# 12v6abuckconverter.net
KiCad netlist of a schematic drawn in EAGLE
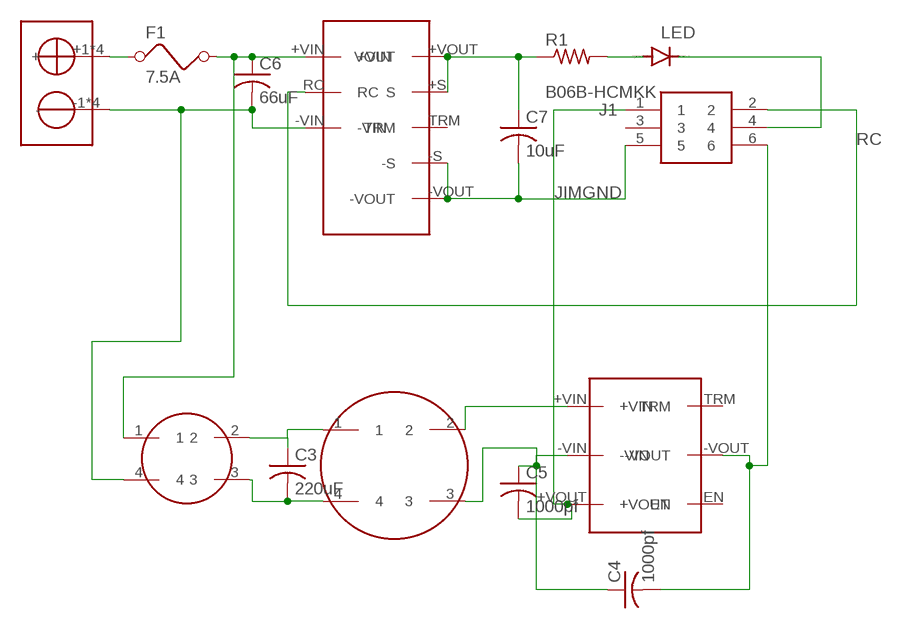
[diagram p0: schematic, sheet 1]

(export (version "E")
  (design (tool "Eeschema 10.0.6"))
  (components
    (comp (ref "BUCK150UH")
      (value "CMNMODECHOKE150UH")
      (footprint "eagle-import:CMNMODECHOKE150UH")
      (libsource (lib "eagle-import") (part "CMNMODECHOKE150UH"))
    )
    (comp (ref "C3")
      (value "220uF")
      (footprint "eagle-import:C0805")
      (libsource (lib "eagle-import") (part "C-USC0805"))
    )
    (comp (ref "C4")
      (value "1000pf")
      (footprint "eagle-import:C0805")
      (libsource (lib "eagle-import") (part "C-USC0805"))
    )
    (comp (ref "C5")
      (value "1000pf")
      (footprint "eagle-import:C0805")
      (libsource (lib "eagle-import") (part "C-USC0805"))
    )
    (comp (ref "C6")
      (value "66uF")
      (footprint "eagle-import:C0805")
      (libsource (lib "eagle-import") (part "C-USC0805"))
    )
    (comp (ref "C7")
      (value "10uF")
      (footprint "eagle-import:C0805")
      (libsource (lib "eagle-import") (part "C-USC0805"))
    )
    (comp (ref "D1")
      (value "BYV95")
      (footprint "eagle-import:SOD57-10")
      (libsource (lib "eagle-import") (part "BYV95"))
    )
    (comp (ref "F1")
      (value "7.5A")
      (footprint "eagle-import:FUSE")
      (libsource (lib "eagle-import") (part "FUSE"))
    )
    (comp (ref "J1")
      (value "B06B-HCMKK")
      (footprint "eagle-import:B06BHCMKK")
      (fields (field (name "MOUSER_PART_NUMBER") "306-B06B-HCMKK"))
      (libsource (lib "eagle-import") (part "B06B-HCMKK"))
    )
    (comp (ref "R1")
      (value "R-US_R0805")
      (footprint "eagle-import:R0805")
      (libsource (lib "eagle-import") (part "R-US_R0805"))
    )
    (comp (ref "U$1")
      (value "12V6ABUCKCONVERTER")
      (footprint "eagle-import:12V6ABUCKCONVERTER")
      (libsource (lib "eagle-import") (part "12V6ABUCKCONVERTER"))
    )
    (comp (ref "U$2")
      (value "SB50")
      (footprint "eagle-import:MINI-SB-50")
      (libsource (lib "eagle-import") (part "SB50"))
    )
    (comp (ref "U$3")
      (value "BUCK1.6A")
      (footprint "eagle-import:BUCK1.6A")
      (libsource (lib "eagle-import") (part "BUCK1.6A"))
    )
    (comp (ref "U$4")
      (value "CMNMODECHOKE1.2MH")
      (footprint "eagle-import:CMNMODECHOKE1.2MH")
      (libsource (lib "eagle-import") (part "CMNMODECHOKE1.2MH"))
    )
  )
  (nets
    (net (code "1") (name "/JIMGND") (class "Default")
      (node (ref "C7") (pin "2") (pinfunction "2_2") (pintype "passive"))
      (node (ref "J1") (pin "5") (pinfunction "5_5") (pintype "bidirectional"))
      (node (ref "U$1") (pin "-S") (pinfunction "-S_-S") (pintype "bidirectional"))
      (node (ref "U$1") (pin "-VOUT") (pinfunction "-VOUT_-VOUT") (pintype "bidirectional"))
    )
    (net (code "2") (name "/LED") (class "Default")
      (node (ref "D1") (pin "C") (pinfunction "C_C") (pintype "passive"))
      (node (ref "J1") (pin "4") (pinfunction "4_4") (pintype "bidirectional"))
    )
    (net (code "3") (name "/RC") (class "Default")
      (node (ref "J1") (pin "2") (pinfunction "2_2") (pintype "bidirectional"))
      (node (ref "U$1") (pin "RC") (pinfunction "RC_RC") (pintype "bidirectional"))
    )
    (net (code "4") (name "Net-(BUCK150UH-Pad1)") (class "Default")
      (node (ref "BUCK150UH") (pin "1") (pinfunction "1_1") (pintype "bidirectional"))
      (node (ref "C6") (pin "1") (pinfunction "1_1") (pintype "passive"))
      (node (ref "F1") (pin "2") (pinfunction "2_2") (pintype "passive"))
      (node (ref "U$1") (pin "+VIN") (pinfunction "+VIN_+VIN") (pintype "bidirectional"))
    )
    (net (code "5") (name "Net-(BUCK150UH-Pad2)") (class "Default")
      (node (ref "BUCK150UH") (pin "2") (pinfunction "2_2") (pintype "bidirectional"))
      (node (ref "C3") (pin "1") (pinfunction "1_1") (pintype "passive"))
      (node (ref "U$4") (pin "1") (pinfunction "1_1") (pintype "bidirectional"))
    )
    (net (code "6") (name "Net-(BUCK150UH-Pad3)") (class "Default")
      (node (ref "BUCK150UH") (pin "3") (pinfunction "3_3") (pintype "bidirectional"))
      (node (ref "C3") (pin "2") (pinfunction "2_2") (pintype "passive"))
      (node (ref "U$4") (pin "4") (pinfunction "4_4") (pintype "bidirectional"))
    )
    (net (code "7") (name "Net-(BUCK150UH-Pad4)") (class "Default")
      (node (ref "BUCK150UH") (pin "4") (pinfunction "4_4") (pintype "bidirectional"))
      (node (ref "C6") (pin "2") (pinfunction "2_2") (pintype "passive"))
      (node (ref "U$1") (pin "-VIN") (pinfunction "-VIN_-VIN") (pintype "bidirectional"))
      (node (ref "U$2") (pin "-1") (pinfunction "-_-1") (pintype "bidirectional"))
      (node (ref "U$2") (pin "-2") (pinfunction "-_-2") (pintype "bidirectional"))
      (node (ref "U$2") (pin "-3") (pinfunction "-_-3") (pintype "bidirectional"))
      (node (ref "U$2") (pin "-4") (pinfunction "-_-4") (pintype "bidirectional"))
    )
    (net (code "8") (name "Net-(C4-Pad1)") (class "Default")
      (node (ref "C4") (pin "1") (pinfunction "1_1") (pintype "passive"))
      (node (ref "C5") (pin "1") (pinfunction "1_1") (pintype "passive"))
      (node (ref "U$3") (pin "-VIN") (pinfunction "-VIN_-VIN") (pintype "bidirectional"))
      (node (ref "U$4") (pin "3") (pinfunction "3_3") (pintype "bidirectional"))
    )
    (net (code "9") (name "Net-(C4-Pad2)") (class "Default")
      (node (ref "C4") (pin "2") (pinfunction "2_2") (pintype "passive"))
      (node (ref "J1") (pin "6") (pinfunction "6_6") (pintype "bidirectional"))
      (node (ref "U$3") (pin "-VOUT") (pinfunction "-VOUT_-VOUT") (pintype "bidirectional"))
    )
    (net (code "10") (name "Net-(C5-Pad2)") (class "Default")
      (node (ref "C5") (pin "2") (pinfunction "2_2") (pintype "passive"))
      (node (ref "J1") (pin "1") (pinfunction "1_1") (pintype "bidirectional"))
      (node (ref "U$3") (pin "+VOUT") (pinfunction "+VOUT_+VOUT") (pintype "bidirectional"))
    )
    (net (code "11") (name "Net-(D1-PadA)") (class "Default")
      (node (ref "D1") (pin "A") (pinfunction "A_A") (pintype "passive"))
      (node (ref "R1") (pin "2") (pinfunction "2_2") (pintype "passive"))
    )
    (net (code "12") (name "Net-(F1-Pad1)") (class "Default")
      (node (ref "F1") (pin "1") (pinfunction "1_1") (pintype "passive"))
      (node (ref "U$2") (pin "+1") (pinfunction "+_+1") (pintype "bidirectional"))
      (node (ref "U$2") (pin "+2") (pinfunction "+_+2") (pintype "bidirectional"))
      (node (ref "U$2") (pin "+3") (pinfunction "+_+3") (pintype "bidirectional"))
      (node (ref "U$2") (pin "+4") (pinfunction "+_+4") (pintype "bidirectional"))
    )
    (net (code "13") (name "Net-(U$1-S)") (class "Default")
      (node (ref "C7") (pin "1") (pinfunction "1_1") (pintype "passive"))
      (node (ref "R1") (pin "1") (pinfunction "1_1") (pintype "passive"))
      (node (ref "U$1") (pin "+S") (pinfunction "S_+S") (pintype "bidirectional"))
      (node (ref "U$1") (pin "+VOUT") (pinfunction "VOUT_+VOUT") (pintype "bidirectional"))
    )
    (net (code "14") (name "Net-(U$3-Pad+VIN)") (class "Default")
      (node (ref "U$3") (pin "+VIN") (pinfunction "+VIN_+VIN") (pintype "bidirectional"))
      (node (ref "U$4") (pin "2") (pinfunction "2_2") (pintype "bidirectional"))
    )
    (net (code "15") (name "unconnected-(J1-Pad3)") (class "Default")
      (node (ref "J1") (pin "3") (pinfunction "3_3") (pintype "bidirectional"))
    )
    (net (code "16") (name "unconnected-(U$1-PadTRM)") (class "Default")
      (node (ref "U$1") (pin "TRM") (pinfunction "TRM_TRM") (pintype "bidirectional"))
    )
    (net (code "17") (name "unconnected-(U$3-PadEN)") (class "Default")
      (node (ref "U$3") (pin "EN") (pinfunction "EN_EN") (pintype "bidirectional"))
    )
    (net (code "18") (name "unconnected-(U$3-PadTRM)") (class "Default")
      (node (ref "U$3") (pin "TRM") (pinfunction "TRM_TRM") (pintype "bidirectional"))
    )
  )
)
